# Recepteur.net
KiCad netlist of a schematic drawn in Altium Designer
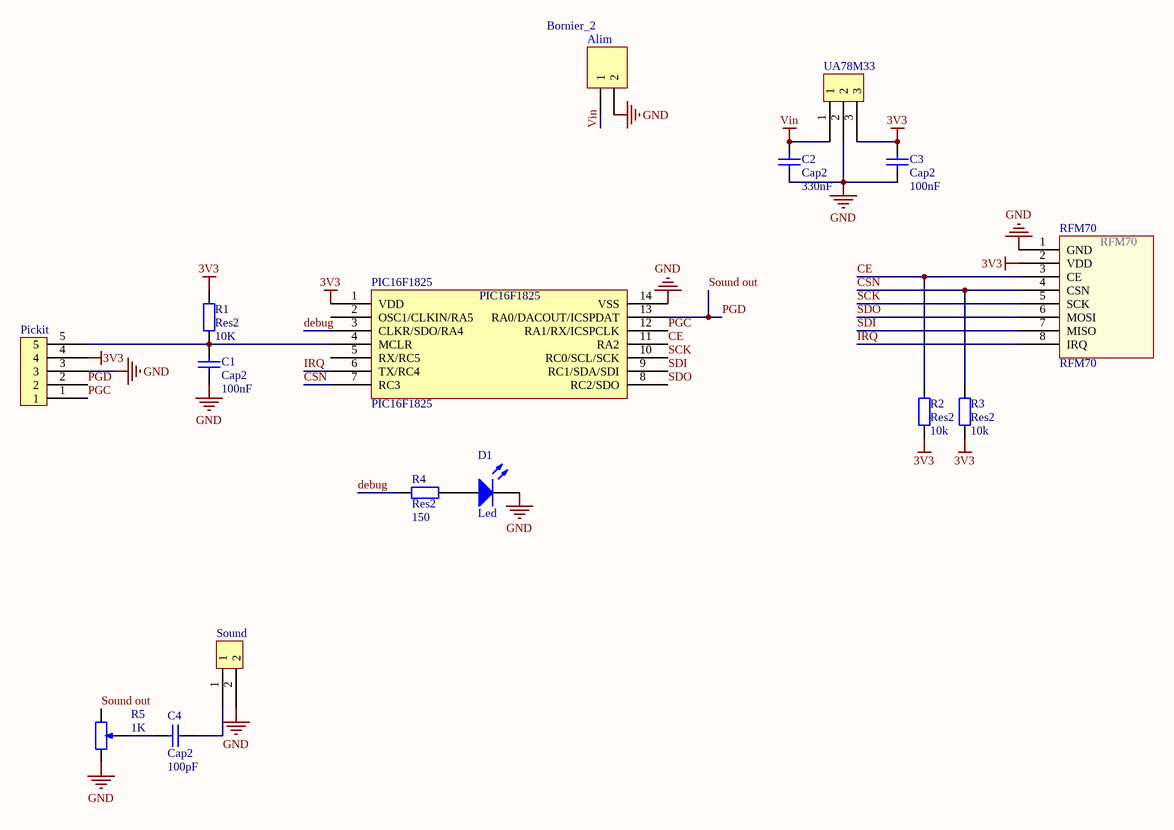
[diagram p0: Recepteur.SchDoc]

(export (version "E")
  (design (tool "Eeschema 10.0.6"))
  (components
    (comp (ref "Alim")
      (value "Bornier_2")
      (footprint "Bornier_2")
      (description "Header, 2-Pin")
      (fields (field (name "PUBLISHER") "Altium Limited"))
      (libsource (lib "INTEGRATED_LIBRARY1_CONNECTEURS") (part "Bornier_2"))
    )
    (comp (ref "C1")
      (value "Cap2")
      (footprint "CAPA2")
      (description "Capacitor")
      (fields (field (name "ALTIUM_VALUE") "100nF") (field (name "PUBLISHER") "Altium Limited"))
      (libsource (lib "LIBRAIRIE_INTEGREE_PHELMA1") (part "Cap2"))
    )
    (comp (ref "C2")
      (value "Cap2")
      (footprint "CAPA2")
      (description "Capacitor")
      (fields (field (name "ALTIUM_VALUE") "330nF") (field (name "PUBLISHER") "Altium Limited"))
      (libsource (lib "LIBRAIRIE_INTEGREE_PHELMA1") (part "Cap2"))
    )
    (comp (ref "C3")
      (value "Cap2")
      (footprint "CAPA2")
      (description "Capacitor")
      (fields (field (name "ALTIUM_VALUE") "100nF") (field (name "PUBLISHER") "Altium Limited"))
      (libsource (lib "LIBRAIRIE_INTEGREE_PHELMA1") (part "Cap2"))
    )
    (comp (ref "C4")
      (value "Cap2")
      (footprint "CAPA2")
      (description "Capacitor")
      (fields (field (name "ALTIUM_VALUE") "100pF") (field (name "PUBLISHER") "Altium Limited"))
      (libsource (lib "LIBRAIRIE_INTEGREE_PHELMA1") (part "Cap2"))
    )
    (comp (ref "D1")
      (value "Led")
      (footprint "LED")
      (description "LED")
      (fields (field (name "PUBLISHER") "Altium Limited"))
      (libsource (lib "LIBRAIRIE_INTEGREE_PHELMA1") (part "Led"))
    )
    (comp (ref "PIC16F1825")
      (value "PIC16F1825")
      (footprint "PIC16F1825")
      (libsource (lib "pic") (part "PIC16F1825"))
    )
    (comp (ref "Pickit")
      (value "CONKK5")
      (footprint "CONKK5")
      (libsource (lib "INTEGRATED_LIBRARY1_CONNECTEURS") (part "CONKK5"))
    )
    (comp (ref "R1")
      (value "Res2")
      (footprint "res5_1/4W")
      (description "Resistor")
      (fields (field (name "ALTIUM_VALUE") "10K") (field (name "PUBLISHER") "Altium Limited"))
      (libsource (lib "") (part "Res2_1"))
    )
    (comp (ref "R2")
      (value "Res2")
      (footprint "res5_1/4W")
      (description "Resistor")
      (fields (field (name "ALTIUM_VALUE") "10k") (field (name "PUBLISHER") "Altium Limited"))
      (libsource (lib "") (part "Res2_1"))
    )
    (comp (ref "R3")
      (value "Res2")
      (footprint "res5_1/4W")
      (description "Resistor")
      (fields (field (name "ALTIUM_VALUE") "10k") (field (name "PUBLISHER") "Altium Limited"))
      (libsource (lib "") (part "Res2_1"))
    )
    (comp (ref "R4")
      (value "Res2")
      (footprint "res5_1/4W")
      (description "Resistor")
      (fields (field (name "ALTIUM_VALUE") "150") (field (name "PUBLISHER") "Altium Limited"))
      (libsource (lib "LIBRAIRIE_INTEGREE_PHELMA1") (part "Res2"))
    )
    (comp (ref "R5")
      (value "1K")
      (footprint "AJUSTABLE")
      (description "Potentiometer")
      (fields (field (name "Comment") "RPot1") (field (name "PUBLISHER") "Altium Limited"))
      (libsource (lib "LIBRAIRIE_INTEGREE_PHELMA1") (part "RPot1"))
    )
    (comp (ref "RFM70") (value "RFM70") (footprint "RFM70") (libsource (lib "pic") (part "RFM70")))
    (comp (ref "Sound")
      (value "CONKK2")
      (footprint "CONKK2")
      (libsource (lib "INTEGRATED_LIBRARY1_CONNECTEURS") (part "CONKK2"))
    )
    (comp (ref "UA78M33")
      (value "CONKK3")
      (footprint "CONKK3")
      (libsource (lib "INTEGRATED_LIBRARY1_CONNECTEURS") (part "CONKK3"))
    )
  )
  (nets
    (net (code "1") (name "/CE") (class "Default")
      (node (ref "PIC16F1825") (pin "11") (pinfunction "RA2_11") (pintype "passive"))
      (node (ref "R2") (pin "2") (pinfunction "2_2") (pintype "passive"))
      (node (ref "RFM70") (pin "3") (pinfunction "CE_3") (pintype "passive"))
    )
    (net (code "2") (name "/CSN") (class "Default")
      (node (ref "PIC16F1825") (pin "7") (pinfunction "RC3_7") (pintype "passive"))
      (node (ref "R3") (pin "2") (pinfunction "2_2") (pintype "passive"))
      (node (ref "RFM70") (pin "4") (pinfunction "CSN_4") (pintype "passive"))
    )
    (net (code "3") (name "/IRQ") (class "Default")
      (node (ref "PIC16F1825") (pin "6") (pinfunction "TX/RC4_6") (pintype "passive"))
      (node (ref "RFM70") (pin "8") (pinfunction "IRQ_8") (pintype "passive"))
    )
    (net (code "4") (name "/PGC") (class "Default")
      (node (ref "PIC16F1825") (pin "12") (pinfunction "RA1/RX/ICSPCLK_12") (pintype "passive"))
      (node (ref "Pickit") (pin "1") (pinfunction "1_1") (pintype "passive"))
    )
    (net (code "5") (name "/PGD") (class "Default")
      (node (ref "PIC16F1825") (pin "13") (pinfunction "RA0/DACOUT/ICSPDAT_13") (pintype "passive"))
      (node (ref "Pickit") (pin "2") (pinfunction "2_2") (pintype "passive"))
      (node (ref "R5") (pin "2") (pinfunction "2_2") (pintype "passive"))
    )
    (net (code "6") (name "/SCK") (class "Default")
      (node (ref "PIC16F1825") (pin "10") (pinfunction "RC0/SCL/SCK_10") (pintype "passive"))
      (node (ref "RFM70") (pin "5") (pinfunction "SCK_5") (pintype "passive"))
    )
    (net (code "7") (name "/SDI") (class "Default")
      (node (ref "PIC16F1825") (pin "9") (pinfunction "RC1/SDA/SDI_9") (pintype "passive"))
      (node (ref "RFM70") (pin "7") (pinfunction "MISO_7") (pintype "passive"))
    )
    (net (code "8") (name "/SDO") (class "Default")
      (node (ref "PIC16F1825") (pin "8") (pinfunction "RC2/SDO_8") (pintype "passive"))
      (node (ref "RFM70") (pin "6") (pinfunction "MOSI_6") (pintype "passive"))
    )
    (net (code "9") (name "/debug") (class "Default")
      (node (ref "PIC16F1825") (pin "3") (pinfunction "CLKR/SDO/RA4_3") (pintype "passive"))
      (node (ref "R4") (pin "1") (pinfunction "1_1") (pintype "passive"))
    )
    (net (code "10") (name "3V3") (class "Default")
      (node (ref "C3") (pin "2") (pinfunction "2_2") (pintype "passive"))
      (node (ref "PIC16F1825") (pin "1") (pinfunction "VDD_1") (pintype "passive"))
      (node (ref "Pickit") (pin "4") (pinfunction "4_4") (pintype "passive"))
      (node (ref "R1") (pin "2") (pinfunction "2_2") (pintype "passive"))
      (node (ref "R2") (pin "1") (pinfunction "1_1") (pintype "passive"))
      (node (ref "R3") (pin "1") (pinfunction "1_1") (pintype "passive"))
      (node (ref "RFM70") (pin "2") (pinfunction "VDD_2") (pintype "passive"))
      (node (ref "UA78M33") (pin "3") (pinfunction "3_3") (pintype "passive"))
    )
    (net (code "11") (name "GND") (class "Default")
      (node (ref "Alim") (pin "2") (pinfunction "2_2") (pintype "passive"))
      (node (ref "C1") (pin "1") (pinfunction "1_1") (pintype "passive"))
      (node (ref "C2") (pin "1") (pinfunction "1_1") (pintype "passive"))
      (node (ref "C3") (pin "1") (pinfunction "1_1") (pintype "passive"))
      (node (ref "D1") (pin "2") (pinfunction "K_2") (pintype "passive"))
      (node (ref "PIC16F1825") (pin "14") (pinfunction "VSS_14") (pintype "passive"))
      (node (ref "Pickit") (pin "3") (pinfunction "3_3") (pintype "passive"))
      (node (ref "R5") (pin "1") (pinfunction "1_1") (pintype "passive"))
      (node (ref "RFM70") (pin "1") (pinfunction "GND_1") (pintype "passive"))
      (node (ref "Sound") (pin "2") (pinfunction "2_2") (pintype "passive"))
      (node (ref "UA78M33") (pin "2") (pinfunction "2_2") (pintype "passive"))
    )
    (net (code "12") (name "Net-(C4-Pad1)") (class "Default")
      (node (ref "C4") (pin "1") (pinfunction "1_1") (pintype "passive"))
      (node (ref "R5") (pin "3") (pinfunction "3_3") (pintype "passive"))
    )
    (net (code "13") (name "Net-(C4-Pad2)") (class "Default")
      (node (ref "C4") (pin "2") (pinfunction "2_2") (pintype "passive"))
      (node (ref "Sound") (pin "1") (pinfunction "1_1") (pintype "passive"))
    )
    (net (code "14") (name "Net-(D1-A)") (class "Default")
      (node (ref "D1") (pin "1") (pinfunction "A_1") (pintype "passive"))
      (node (ref "R4") (pin "2") (pinfunction "2_2") (pintype "passive"))
    )
    (net (code "15") (name "Net-(PIC16F1825-MCLR)") (class "Default")
      (node (ref "C1") (pin "2") (pinfunction "2_2") (pintype "passive"))
      (node (ref "PIC16F1825") (pin "4") (pinfunction "MCLR_4") (pintype "passive"))
      (node (ref "Pickit") (pin "5") (pinfunction "5_5") (pintype "passive"))
      (node (ref "R1") (pin "1") (pinfunction "1_1") (pintype "passive"))
    )
    (net (code "16") (name "Vin") (class "Default")
      (node (ref "Alim") (pin "1") (pinfunction "1_1") (pintype "passive"))
      (node (ref "C2") (pin "2") (pinfunction "2_2") (pintype "passive"))
      (node (ref "UA78M33") (pin "1") (pinfunction "1_1") (pintype "passive"))
    )
    (net (code "17") (name "unconnected-(PIC16F1825-OSC1{slash}CLKIN{slash}RA5-Pad2)") (class "Default")
      (node (ref "PIC16F1825") (pin "2") (pinfunction "OSC1/CLKIN/RA5_2") (pintype "passive"))
    )
    (net (code "18") (name "unconnected-(PIC16F1825-RX{slash}RC5-Pad5)") (class "Default")
      (node (ref "PIC16F1825") (pin "5") (pinfunction "RX/RC5_5") (pintype "passive"))
    )
  )
)
